# TPS5450.net
KiCad netlist of a schematic drawn in Altium Designer
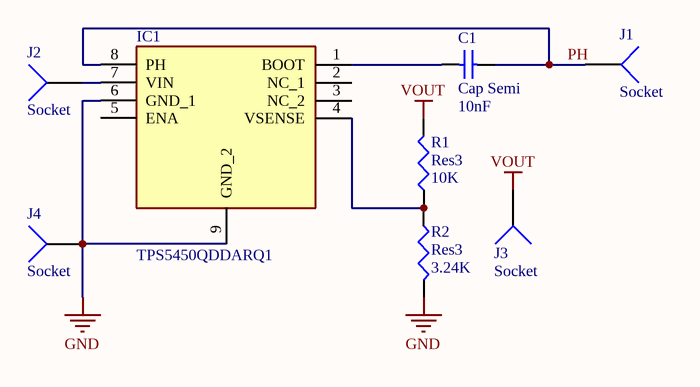
[diagram p0: TPS5450.SchDoc]

(export (version "E")
  (design (tool "Eeschema 10.0.6"))
  (components
    (comp (ref "C1")
      (value "Cap Semi")
      (footprint "1608[0603]")
      (description "Capacitor (Semiconductor SIM Model)")
      (fields (field (name "ALTIUM_VALUE") "10nF") (field (name "PUBLISHER") "Altium Limited"))
      (libsource (lib "Miscellaneous Devices") (part "Cap Semi"))
    )
    (comp (ref "IC1")
      (value "TPS5450QDDARQ1")
      (footprint "SamacSys:SOIC127P600X170-9N")
      (description "Integrated Circuit")
      (fields (field (name "MOUSER PART NUMBER") "595-TPS5450QDDARQ1"))
      (libsource (lib "*") (part "TPS5450QDDARQ1"))
    )
    (comp (ref "J1")
      (value "Socket")
      (footprint "PIN1")
      (fields (field (name "PUBLISHER") "Altium Limited"))
      (libsource (lib "Miscellaneous Connectors") (part "Socket"))
    )
    (comp (ref "J2")
      (value "Socket")
      (footprint "PIN1")
      (fields (field (name "PUBLISHER") "Altium Limited"))
      (libsource (lib "Miscellaneous Connectors") (part "Socket"))
    )
    (comp (ref "J3")
      (value "Socket")
      (footprint "PIN1")
      (fields (field (name "PUBLISHER") "Altium Limited"))
      (libsource (lib "Miscellaneous Connectors") (part "Socket"))
    )
    (comp (ref "J4")
      (value "Socket")
      (footprint "PIN1")
      (fields (field (name "PUBLISHER") "Altium Limited"))
      (libsource (lib "Miscellaneous Connectors") (part "Socket"))
    )
    (comp (ref "R1")
      (value "Res3")
      (footprint "J1-0603")
      (description "Resistor")
      (fields (field (name "ALTIUM_VALUE") "10K") (field (name "PUBLISHER") "Altium Limited"))
      (libsource (lib "Miscellaneous Devices") (part "Res3"))
    )
    (comp (ref "R2")
      (value "Res3")
      (footprint "J1-0603")
      (description "Resistor")
      (fields (field (name "ALTIUM_VALUE") "3.24K") (field (name "PUBLISHER") "Altium Limited"))
      (libsource (lib "Miscellaneous Devices") (part "Res3"))
    )
  )
  (nets
    (net (code "1") (name "/PH") (class "Default")
      (node (ref "C1") (pin "2") (pinfunction "2_2") (pintype "passive"))
      (node (ref "IC1") (pin "8") (pinfunction "PH_8") (pintype "passive"))
      (node (ref "J1") (pin "1") (pinfunction "1_1") (pintype "passive"))
    )
    (net (code "2") (name "GND") (class "Default")
      (node (ref "IC1") (pin "6") (pinfunction "GND_1_6") (pintype "passive"))
      (node (ref "IC1") (pin "9") (pinfunction "GND_2_9") (pintype "passive"))
      (node (ref "J4") (pin "1") (pinfunction "1_1") (pintype "passive"))
      (node (ref "R2") (pin "2") (pinfunction "2_2") (pintype "passive"))
    )
    (net (code "3") (name "Net-(IC1-BOOT)") (class "Default")
      (node (ref "C1") (pin "1") (pinfunction "1_1") (pintype "passive"))
      (node (ref "IC1") (pin "1") (pinfunction "BOOT_1") (pintype "passive"))
    )
    (net (code "4") (name "Net-(IC1-VIN)") (class "Default")
      (node (ref "IC1") (pin "7") (pinfunction "VIN_7") (pintype "passive"))
      (node (ref "J2") (pin "1") (pinfunction "1_1") (pintype "passive"))
    )
    (net (code "5") (name "Net-(IC1-VSENSE)") (class "Default")
      (node (ref "IC1") (pin "4") (pinfunction "VSENSE_4") (pintype "passive"))
      (node (ref "R1") (pin "1") (pinfunction "1_1") (pintype "passive"))
      (node (ref "R2") (pin "1") (pinfunction "1_1") (pintype "passive"))
    )
    (net (code "6") (name "VOUT") (class "Default")
      (node (ref "J3") (pin "1") (pinfunction "1_1") (pintype "passive"))
      (node (ref "R1") (pin "2") (pinfunction "2_2") (pintype "passive"))
    )
    (net (code "7") (name "unconnected-(IC1-ENA-Pad5)") (class "Default")
      (node (ref "IC1") (pin "5") (pinfunction "ENA_5") (pintype "passive"))
    )
    (net (code "8") (name "unconnected-(IC1-NC_1-Pad2)") (class "Default")
      (node (ref "IC1") (pin "2") (pinfunction "NC_1_2") (pintype "passive"))
    )
    (net (code "9") (name "unconnected-(IC1-NC_2-Pad3)") (class "Default")
      (node (ref "IC1") (pin "3") (pinfunction "NC_2_3") (pintype "passive"))
    )
  )
)
